# v1_0.net
KiCad netlist of a schematic drawn in Altium Designer
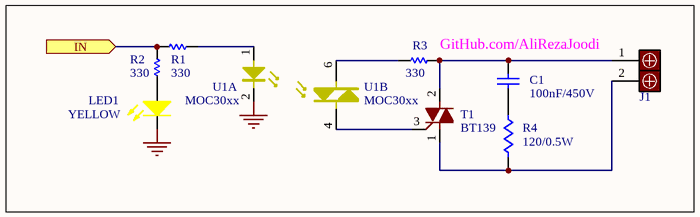
[diagram p0: v1.0.SchDoc]

(export (version "E")
  (design (tool "Eeschema 10.0.6"))
  (components
    (comp (ref "C1")
      (value "100nF/450V")
      (footprint "CAPR7.62-6.8x5")
      (description "Capacitor")
      (fields (field (name "MANUFACTURER") "Generic Components") (field (name "PUBLISHER") "Altium Limited"))
      (libsource (lib "Miscellaneous Devices") (part "Cap"))
    )
    (comp (ref "J1")
      (value "2PIN")
      (footprint "Connector_Phoenix_2PIN_MSTB")
      (description "Connector, Header, 2Pin")
      (libsource (lib "Connector") (part "Connector1x2_Power2"))
    )
    (comp (ref "LED1")
      (value "YELLOW")
      (footprint "LED_THD_3MM_YELLOW_R")
      (description "LED, Yellow")
      (fields (field (name "MANUFACTURER") "Generic Components") (field (name "PUBLISHER") "Altium Limited"))
      (libsource (lib "Display") (part "LED_YELLOW"))
    )
    (comp (ref "R1")
      (value "330")
      (footprint "R_THD_AXIAL0.4(1/4W)")
      (description "Resistor")
      (libsource (lib "Passive") (part "Resistor"))
    )
    (comp (ref "R2")
      (value "330")
      (footprint "R_THD_AXIAL0.4(1/4W)")
      (description "Resistor")
      (libsource (lib "Passive") (part "Resistor"))
    )
    (comp (ref "R3")
      (value "330")
      (footprint "R_THD_AXIAL0.4(1/4W)")
      (description "Resistor")
      (libsource (lib "Passive") (part "Resistor"))
    )
    (comp (ref "R4")
      (value "120/0.5W")
      (footprint "AXIAL-0.4")
      (description "Resistor")
      (fields (field (name "MANUFACTURER") "Generic Components") (field (name "PUBLISHER") "Altium Limited"))
      (libsource (lib "Miscellaneous Devices") (part "Res1"))
    )
    (comp (ref "T1")
      (value "BT139")
      (footprint "TO220_3PIN_V")
      (description "Triac,")
      (libsource (lib "Passive") (part "Triac"))
    )
    (comp (ref "U1")
      (value "MOC30xx")
      (footprint "DIP_6")
      (description "Opto-Triac")
      (libsource (lib "Other_Myself") (part "MOC3021"))
    )
  )
  (nets
    (net (code "1") (name "/IN") (class "Default")
      (node (ref "R1") (pin "1") (pinfunction "1_1") (pintype "passive"))
      (node (ref "R2") (pin "2") (pinfunction "2_2") (pintype "passive"))
    )
    (net (code "2") (name "GND") (class "Default")
      (node (ref "LED1") (pin "2") (pinfunction "K_2") (pintype "passive"))
      (node (ref "U1") (pin "2") (pinfunction "K_2") (pintype "power_in"))
    )
    (net (code "3") (name "Net-(C1-Pad1)") (class "Default")
      (node (ref "C1") (pin "1") (pinfunction "1_1") (pintype "passive"))
      (node (ref "R4") (pin "2") (pinfunction "2_2") (pintype "passive"))
    )
    (net (code "4") (name "Net-(LED1-A)") (class "Default")
      (node (ref "LED1") (pin "1") (pinfunction "A_1") (pintype "passive"))
      (node (ref "R2") (pin "1") (pinfunction "1_1") (pintype "passive"))
    )
    (net (code "5") (name "Net-(R3-Pad1)") (class "Default")
      (node (ref "R3") (pin "1") (pinfunction "1_1") (pintype "passive"))
      (node (ref "U1") (pin "6") (pinfunction "A/K_6") (pintype "passive"))
    )
    (net (code "6") (name "Net-(T1-G)") (class "Default")
      (node (ref "T1") (pin "3") (pinfunction "G_3") (pintype "passive"))
      (node (ref "U1") (pin "4") (pinfunction "A/K_4") (pintype "passive"))
    )
    (net (code "7") (name "Net-(T1-T1)") (class "Default")
      (node (ref "J1") (pin "2") (pinfunction "2_2") (pintype "passive"))
      (node (ref "R4") (pin "1") (pinfunction "1_1") (pintype "passive"))
      (node (ref "T1") (pin "1") (pinfunction "T1_1") (pintype "passive"))
    )
    (net (code "8") (name "Net-(T1-T2)") (class "Default")
      (node (ref "C1") (pin "2") (pinfunction "2_2") (pintype "passive"))
      (node (ref "J1") (pin "1") (pinfunction "1_1") (pintype "passive"))
      (node (ref "R3") (pin "2") (pinfunction "2_2") (pintype "passive"))
      (node (ref "T1") (pin "2") (pinfunction "T2_2") (pintype "passive"))
    )
    (net (code "9") (name "Net-(U1A-A)") (class "Default")
      (node (ref "R1") (pin "2") (pinfunction "2_2") (pintype "passive"))
      (node (ref "U1") (pin "1") (pinfunction "A_1") (pintype "power_in"))
    )
  )
)
